# UKHASnetLPC.net
KiCad netlist of a schematic drawn in EAGLE
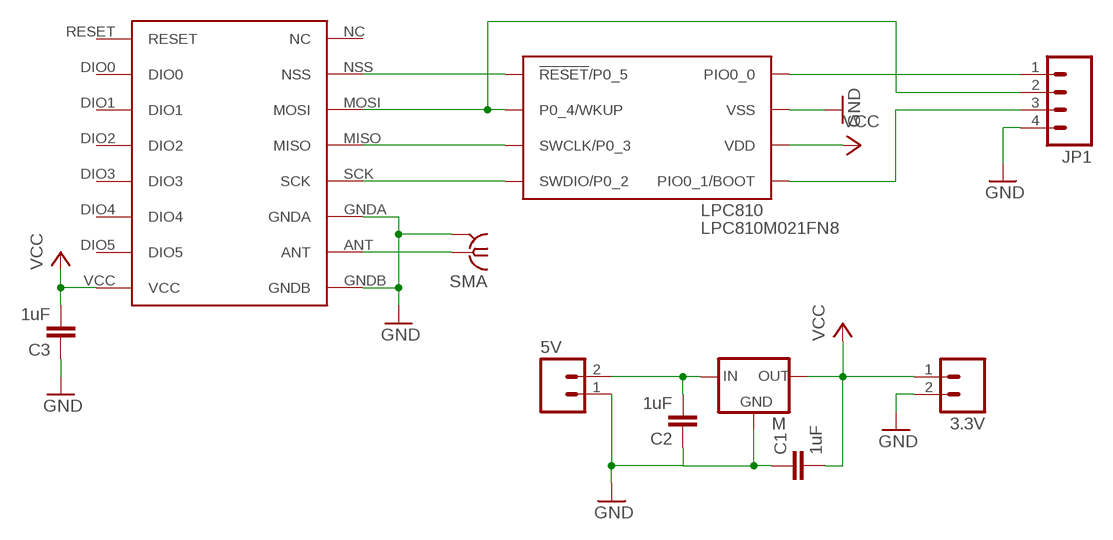
[diagram p0: schematic, sheet 1]

(export (version "E")
  (design (tool "Eeschema 10.0.6"))
  (components
    (comp (ref "3.3V")
      (value "M02LOCK")
      (footprint "eagle-import:1X02_LOCK")
      (libsource (lib "eagle-import") (part "M02LOCK"))
    )
    (comp (ref "5V")
      (value "M02LOCK")
      (footprint "eagle-import:1X02_LOCK")
      (libsource (lib "eagle-import") (part "M02LOCK"))
    )
    (comp (ref "C1")
      (value "1uF")
      (footprint "eagle-import:CAP-PTH-SMALL")
      (libsource (lib "eagle-import") (part "CAPPTH"))
    )
    (comp (ref "C2")
      (value "1uF")
      (footprint "eagle-import:CAP-PTH-SMALL")
      (libsource (lib "eagle-import") (part "CAPPTH"))
    )
    (comp (ref "C3")
      (value "1uF")
      (footprint "eagle-import:CAP-PTH-SMALL")
      (libsource (lib "eagle-import") (part "CAPPTH"))
    )
    (comp (ref "JP1")
      (value "M04PTH")
      (footprint "eagle-import:1X04")
      (libsource (lib "eagle-import") (part "M04PTH"))
    )
    (comp (ref "LPC810")
      (value "LPC810M021FN8")
      (footprint "eagle-import:DIP8")
      (libsource (lib "eagle-import") (part "LPC810M021FN8"))
    )
    (comp (ref "M")
      (value "MCP1700INLINE")
      (footprint "eagle-import:TO92-INLINE")
      (libsource (lib "eagle-import") (part "MCP1700INLINE"))
    )
    (comp (ref "RFM69")
      (value "RFM69HW")
      (footprint "eagle-import:RFM")
      (libsource (lib "eagle-import") (part "RFM69HW"))
    )
    (comp (ref "SMA")
      (value "BUS-SMA")
      (footprint "eagle-import:BUS-SMA")
      (libsource (lib "eagle-import") (part "BUS-SMA"))
    )
  )
  (nets
    (net (code "1") (name "GND") (class "Default")
      (node (ref "3.3V") (pin "2") (pinfunction "2_2") (pintype "passive"))
      (node (ref "5V") (pin "1") (pinfunction "1_1") (pintype "passive"))
      (node (ref "C1") (pin "1") (pinfunction "1_1") (pintype "passive"))
      (node (ref "C2") (pin "1") (pinfunction "1_1") (pintype "passive"))
      (node (ref "C3") (pin "1") (pinfunction "1_1") (pintype "passive"))
      (node (ref "JP1") (pin "4") (pinfunction "4_4") (pintype "passive"))
      (node (ref "LPC810") (pin "P$7") (pinfunction "VSS_P$7") (pintype "bidirectional"))
      (node (ref "M") (pin "1") (pinfunction "GND_1") (pintype "input"))
      (node (ref "RFM69") (pin "GNDA") (pinfunction "GNDA_GNDA") (pintype "bidirectional"))
      (node (ref "RFM69") (pin "GNDB") (pinfunction "GNDB_GNDB") (pintype "bidirectional"))
      (node (ref "SMA") (pin "2") (pinfunction "GND_2") (pintype "power_in"))
      (node (ref "SMA") (pin "3") (pinfunction "GND_3") (pintype "power_in"))
      (node (ref "SMA") (pin "4") (pinfunction "GND_4") (pintype "power_in"))
      (node (ref "SMA") (pin "5") (pinfunction "GND_5") (pintype "power_in"))
    )
    (net (code "2") (name "Net-(LPC810-P0_4{slash}WKUP)") (class "Default")
      (node (ref "JP1") (pin "2") (pinfunction "2_2") (pintype "passive"))
      (node (ref "LPC810") (pin "P$2") (pinfunction "P0_4/WKUP_P$2") (pintype "bidirectional"))
      (node (ref "RFM69") (pin "MOSI") (pinfunction "MOSI_MOSI") (pintype "bidirectional"))
    )
    (net (code "3") (name "Net-(LPC810-PIO0_0)") (class "Default")
      (node (ref "JP1") (pin "1") (pinfunction "1_1") (pintype "passive"))
      (node (ref "LPC810") (pin "P$8") (pinfunction "PIO0_0_P$8") (pintype "bidirectional"))
    )
    (net (code "4") (name "Net-(LPC810-PIO0_1{slash}BOOT)") (class "Default")
      (node (ref "JP1") (pin "3") (pinfunction "3_3") (pintype "passive"))
      (node (ref "LPC810") (pin "P$5") (pinfunction "PIO0_1/BOOT_P$5") (pintype "bidirectional"))
    )
    (net (code "5") (name "Net-(LPC810-SWCLK{slash}P0_3)") (class "Default")
      (node (ref "LPC810") (pin "P$3") (pinfunction "SWCLK/P0_3_P$3") (pintype "bidirectional"))
      (node (ref "RFM69") (pin "MISO") (pinfunction "MISO_MISO") (pintype "bidirectional"))
    )
    (net (code "6") (name "Net-(LPC810-SWDIO{slash}P0_2)") (class "Default")
      (node (ref "LPC810") (pin "P$4") (pinfunction "SWDIO/P0_2_P$4") (pintype "bidirectional"))
      (node (ref "RFM69") (pin "SCK") (pinfunction "SCK_SCK") (pintype "bidirectional"))
    )
    (net (code "7") (name "Net-(LPC810-~{RESET}{slash}P0_5)") (class "Default")
      (node (ref "LPC810") (pin "P$1") (pinfunction "~{RESET}/P0_5_P$1") (pintype "bidirectional"))
      (node (ref "RFM69") (pin "NSS") (pinfunction "NSS_NSS") (pintype "bidirectional"))
    )
    (net (code "8") (name "Net-(M-IN)") (class "Default")
      (node (ref "5V") (pin "2") (pinfunction "2_2") (pintype "passive"))
      (node (ref "C2") (pin "2") (pinfunction "2_2") (pintype "passive"))
      (node (ref "M") (pin "2") (pinfunction "IN_2") (pintype "input"))
    )
    (net (code "9") (name "Net-(RFM69-PadANT)") (class "Default")
      (node (ref "RFM69") (pin "ANT") (pinfunction "ANT_ANT") (pintype "bidirectional"))
      (node (ref "SMA") (pin "1") (pinfunction "1_1") (pintype "passive"))
    )
    (net (code "10") (name "VCC") (class "Default")
      (node (ref "3.3V") (pin "1") (pinfunction "1_1") (pintype "passive"))
      (node (ref "C1") (pin "2") (pinfunction "2_2") (pintype "passive"))
      (node (ref "C3") (pin "2") (pinfunction "2_2") (pintype "passive"))
      (node (ref "LPC810") (pin "P$6") (pinfunction "VDD_P$6") (pintype "bidirectional"))
      (node (ref "M") (pin "3") (pinfunction "OUT_3") (pintype "passive"))
      (node (ref "RFM69") (pin "VCC") (pinfunction "VCC_VCC") (pintype "bidirectional"))
    )
    (net (code "11") (name "unconnected-(RFM69-PadDIO0)") (class "Default")
      (node (ref "RFM69") (pin "DIO0") (pinfunction "DIO0_DIO0") (pintype "bidirectional"))
    )
    (net (code "12") (name "unconnected-(RFM69-PadDIO1)") (class "Default")
      (node (ref "RFM69") (pin "DIO1") (pinfunction "DIO1_DIO1") (pintype "bidirectional"))
    )
    (net (code "13") (name "unconnected-(RFM69-PadDIO2)") (class "Default")
      (node (ref "RFM69") (pin "DIO2") (pinfunction "DIO2_DIO2") (pintype "bidirectional"))
    )
    (net (code "14") (name "unconnected-(RFM69-PadDIO3)") (class "Default")
      (node (ref "RFM69") (pin "DIO3") (pinfunction "DIO3_DIO3") (pintype "bidirectional"))
    )
    (net (code "15") (name "unconnected-(RFM69-PadDIO4)") (class "Default")
      (node (ref "RFM69") (pin "DIO4") (pinfunction "DIO4_DIO4") (pintype "bidirectional"))
    )
    (net (code "16") (name "unconnected-(RFM69-PadDIO5)") (class "Default")
      (node (ref "RFM69") (pin "DIO5") (pinfunction "DIO5_DIO5") (pintype "bidirectional"))
    )
    (net (code "17") (name "unconnected-(RFM69-PadNC)") (class "Default")
      (node (ref "RFM69") (pin "NC") (pinfunction "NC_NC") (pintype "bidirectional"))
    )
    (net (code "18") (name "unconnected-(RFM69-PadRESET)") (class "Default")
      (node (ref "RFM69") (pin "RESET") (pinfunction "RESET_RESET") (pintype "bidirectional"))
    )
  )
)
